# PMP9517.net
KiCad netlist of a schematic drawn in Altium Designer
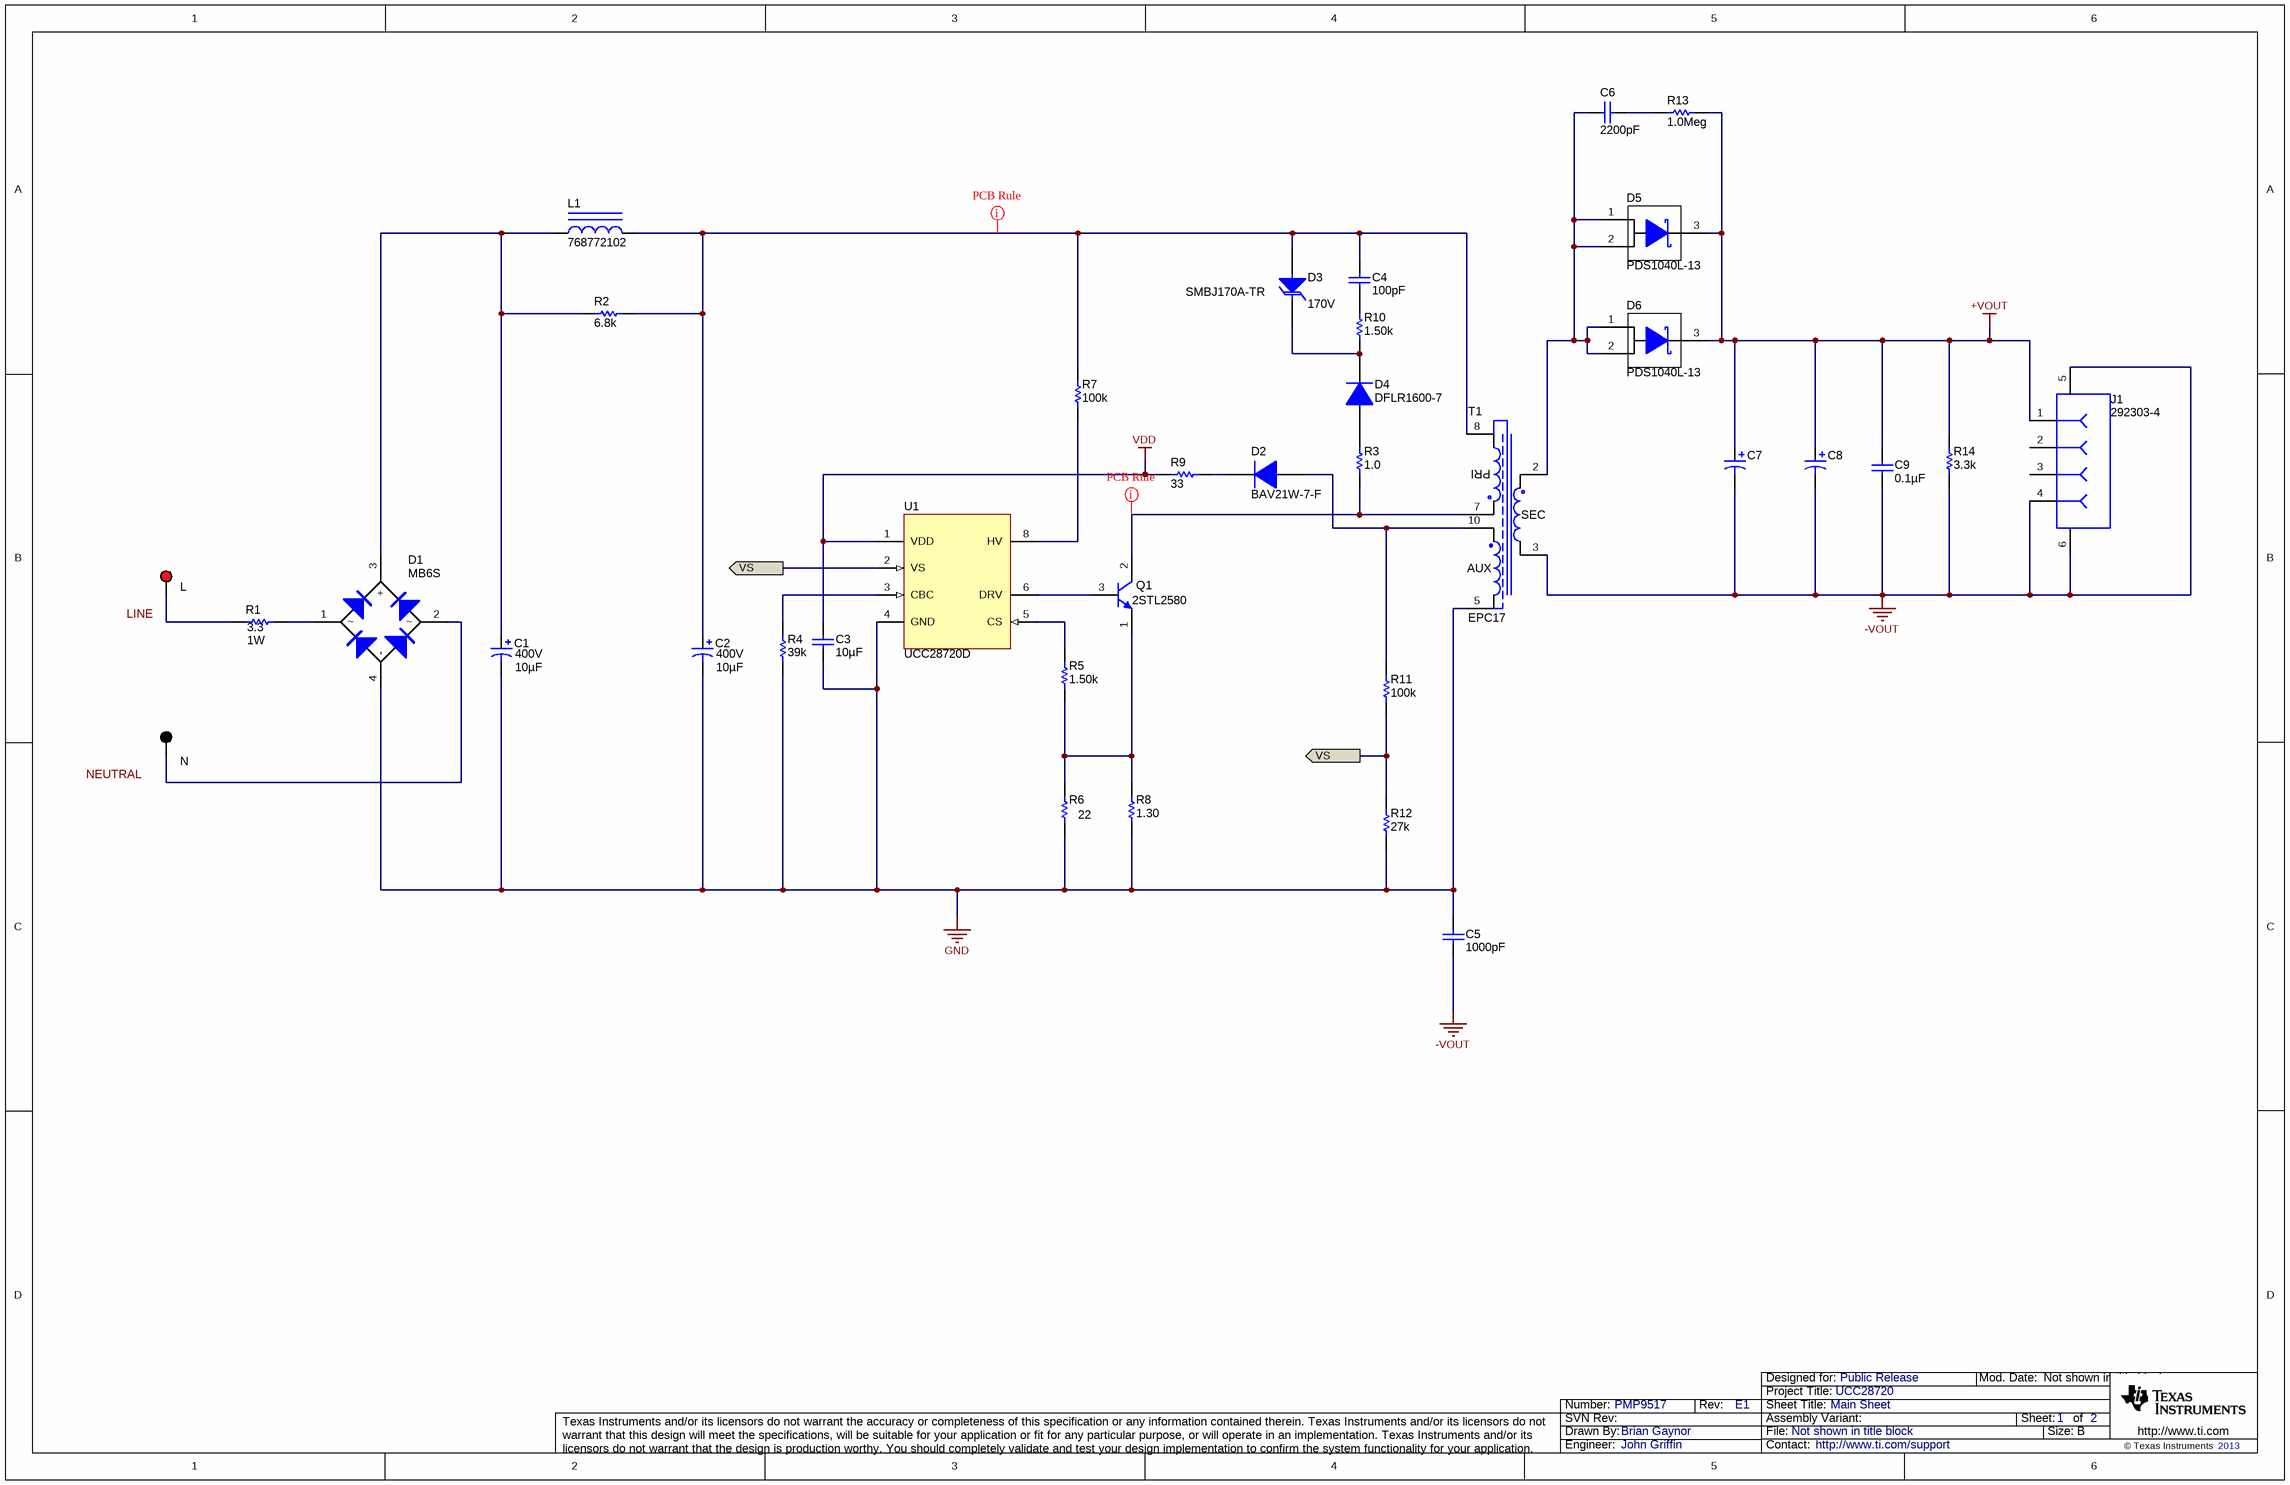
[diagram p0: PMP9517.SchDoc]

(export (version "E")
  (design (tool "Eeschema 10.0.6"))
  (components
    (comp (ref "C1")
      (value "10µF")
      (footprint "CAPPRD500W60D1000H1250")
      (description "CAP ALUM 10UF 400V 20% RADIAL")
      (fields (field (name "PARTNUMBER") "UVC2G100MPD") (field (name "VDC_V") "400V"))
      (libsource (lib "MiscParts") (part "Capacitor_Polarized"))
    )
    (comp (ref "C2")
      (value "10µF")
      (footprint "CAPPRD500W60D1000H1250")
      (description "CAP ALUM 10UF 400V 20% RADIAL")
      (fields (field (name "PARTNUMBER") "UVC2G100MPD") (field (name "VDC_V") "400V"))
      (libsource (lib "MiscParts") (part "Capacitor_Polarized"))
    )
    (comp (ref "C3")
      (value "1210YD106KAT2A")
      (footprint "1210")
      (description "CAP, CERM, 10uF, 16V, +/-10%, X5R, 1210")
      (fields
        (field (name "MANUFACTURER") "AVX")
        (field (name "VALUEDISPLAYED") "10µF")
        (field (name "PUBLISHER") "Texas Instruments")
      )
      (libsource (lib "Capacitor_Ceramic") (part "1210YD106KAT2A"))
    )
    (comp (ref "C4")
      (value "C1206C101JCGACTU")
      (footprint "1206")
      (description "CAP, CERM, 100pF, 500V, +/-5%, C0G/NP0, 1206")
      (fields
        (field (name "MANUFACTURER") "Kemet")
        (field (name "VALUEDISPLAYED") "100pF")
        (field (name "PUBLISHER") "Texas Instruments")
      )
      (libsource (lib "Capacitor_Ceramic") (part "C1206C101JCGACTU"))
    )
    (comp (ref "C5")
      (value "VY2102M29Y5UG63V7")
      (footprint "CAPRD750W60D750H1050")
      (description "CAP, CERM, 1000pF, 300V, +/-20%, Y5U, Radial Disc 7.5mm, ls=7.5")
      (fields
        (field (name "VALUEDISPLAYED") "1000pF")
        (field (name "MANUFACTURER") "Vishay-Bccomponents")
        (field (name "PUBLISHER") "Texas Instruments")
      )
      (libsource (lib "Capacitor_Ceramic") (part "VY2102M29Y5UG63V7"))
    )
    (comp (ref "C6")
      (value "08055C222KAT2A")
      (footprint "0805_HV")
      (description "CAP, CERM, 2200pF, 50V, +/-10%, X7R, 0805")
      (fields
        (field (name "VALUEDISPLAYED") "2200pF")
        (field (name "MANUFACTURER") "AVX")
        (field (name "PUBLISHER") "Texas Instruments")
      )
      (libsource (lib "Capacitor_Ceramic") (part "08055C222KAT2A"))
    )
    (comp (ref "C7")
      (value "RNE0J122MDN1PX")
      (footprint "NRE-AX_800x1080")
      (description "CAP ALUM 1200UF 6.3V 20% RADIAL")
      (fields (field (name "MANUFACTURER") "Nichicon"))
      (libsource (lib "MiscParts") (part "Capacitor_Polarized"))
    )
    (comp (ref "C8")
      (value "CAP ALUM 1200UF 6.3V 20% RADIAL")
      (footprint "NRE-AX_800x1080")
      (description "CAP, [Technology], xxxF, xxV, +/-xx%, xxOhm ESR, [MountType]")
      (fields (field (name "PARTNUMBER") "RNE0J122MDN1PX") (field (name "MANUFACTURER") "Nichicon"))
      (libsource (lib "MiscParts") (part "Capacitor_Polarized"))
    )
    (comp (ref "C9")
      (value "08055C104JAT2A")
      (footprint "0805_HV")
      (description "CAP, CERM, 0.1uF, 50V, +/-5%, X7R, 0805")
      (fields
        (field (name "VALUEDISPLAYED") "0.1µF")
        (field (name "MANUFACTURER") "AVX")
        (field (name "PUBLISHER") "Texas Instruments")
      )
      (libsource (lib "Capacitor_Ceramic") (part "08055C104JAT2A"))
    )
    (comp (ref "D1")
      (value "MB6S")
      (footprint "MiniDIP-MB6S")
      (description "Diode, Switching-Bridge, 600V, 1A, TH")
      (fields (field (name "PARTNUMBER") "MB6S"))
      (libsource (lib "PMP9045E1") (part "MB6S"))
    )
    (comp (ref "D2")
      (value "BAV21W-7-F")
      (footprint "SOD-123")
      (description "Diode, Switching, 200V, 0.2A, SOD-123")
      (fields
        (field (name "MANUFACTURER") "Diodes Inc.")
        (field (name "PARTNUMBER") "BAV21W-7-F")
        (field (name "PUBLISHER") "Texas Instruments")
      )
      (libsource (lib "Diode") (part "BAV21W-7-F"))
    )
    (comp (ref "D3")
      (value "SMBJ170A-TR")
      (footprint "SMB")
      (description "Diode, TVS, Uni, 170V, 600W, SMB")
      (fields
        (field (name "ALTIUM_VALUE") "170V")
        (field (name "MANUFACTURER") "ST Microelectronics")
        (field (name "PUBLISHER") "Texas Instruments")
      )
      (libsource (lib "ZenerDiodes") (part "SMBJ170A-TR"))
    )
    (comp (ref "D4")
      (value "DFLR1600-7")
      (footprint "powerDI123")
      (description "DIODE GP 600V 1A POWERDI123")
      (fields (field (name "MANUFACTURER") "Diodes Inc"))
      (libsource (lib "MiscParts") (part "Diode"))
    )
    (comp (ref "D5")
      (value "PDS1040L-13")
      (footprint "powerdi5")
      (description "DIODE SCHOTTKY 40V 10A POWERDI5")
      (fields (field (name "MANUFACTURER") "Diodes Inc"))
      (libsource (lib "Diode") (part "30WQ04FNPBF"))
    )
    (comp (ref "D6")
      (value "PDS1040L-13")
      (footprint "powerdi5")
      (description "DIODE SCHOTTKY 40V 10A POWERDI5")
      (fields (field (name "MANUFACTURER") "Diodes Inc"))
      (libsource (lib "Diode") (part "30WQ04FNPBF"))
    )
    (comp (ref "J1")
      (value "292303-4")
      (footprint "CONN_TE_292303-4")
      (description "Connector, USB Type A, Receptacle, R/A, TH")
      (fields
        (field (name "MANUFACTURER") "TE Connectivity")
        (field (name "SYMBOLCREATOR") "a0412235")
        (field (name "PUBLISHER") "Texas Instruments")
      )
      (libsource (lib "Connectors") (part "292303-4"))
    )
    (comp (ref "L")
      (value "5005")
      (footprint "Keystone5005")
      (description "Test Point, Compact, Red, TH")
      (fields (field (name "MANUFACTURER") "Keystone") (field (name "PUBLISHER") "Texas Instruments"))
      (libsource (lib "Connectors") (part "5005"))
    )
    (comp (ref "L1")
      (value "768772102")
      (footprint "IND_WE-TI_8095")
      (description "Inductor, Shielded Drum Core, Metal Composite, 1mH, 0.5A, 1.7 ohm, TH")
      (fields
        (field (name "MANUFACTURER") "Wurth Elektronik eiSos")
        (field (name "PUBLISHER") "Texas Instruments")
      )
      (libsource (lib "Inductor_Wurth") (part "768772102"))
    )
    (comp (ref "N")
      (value "5006")
      (footprint "Keystone5006")
      (description "Test Point, Compact, Black, TH")
      (fields (field (name "MANUFACTURER") "Keystone") (field (name "PUBLISHER") "Texas Instruments"))
      (libsource (lib "Connectors") (part "5006"))
    )
    (comp (ref "Q1")
      (value "2STL2580")
      (footprint "TO-92_AllBent")
      (description "Transistors Bipolar - BJT High Volt NPN Trans 800V Vces 400V Vceo")
      (fields (field (name "PARTNUMBER") "2STL2580") (field (name "MANUFACTURER") "STMicroelectronics"))
      (libsource (lib "Bipolar_Transistor") (part "STBV32-AP, ST Microelectronics"))
    )
    (comp (ref "R1")
      (value "3.3")
      (footprint "RES_ERG1S_V")
      (description "RES 3.3 OHM 1W 5% AXIAL")
      (fields (field (name "PARTNUMBER") "SPP1UL3R30JLF") (field (name "POWER_W") "1W"))
      (libsource (lib "MiscParts") (part "Resistor"))
    )
    (comp (ref "R2")
      (value "6.8k")
      (footprint "0805_HV")
      (description "RES, 6.8k ohm, 5%, 0.125W, 0805")
      (fields
        (field (name "PARTNUMBER") "CRCW08056K80JNEA")
        (field (name "MANUFACTURER") "Vishay-Dale")
        (field (name "PUBLISHER") "Texas Instruments")
      )
      (libsource (lib "Resistor_0805") (part "CRCW08056K80JNEA"))
    )
    (comp (ref "R3")
      (value "1.0")
      (footprint "1206")
      (description "RES, 1.0 ohm, 5%, 0.25W, 1206")
      (fields
        (field (name "PARTNUMBER") "CRCW12061R00JNEA")
        (field (name "MANUFACTURER") "Vishay-Dale")
        (field (name "PUBLISHER") "Texas Instruments")
      )
      (libsource (lib "Resistor_1206") (part "CRCW12061R00JNEA"))
    )
    (comp (ref "R4")
      (value "39k")
      (footprint "0603")
      (description "RES, 39k ohm, 5%, 0.1W, 0603")
      (fields
        (field (name "PARTNUMBER") "CRCW060339K0JNEA")
        (field (name "MANUFACTURER") "Vishay-Dale")
        (field (name "PUBLISHER") "Texas Instruments")
      )
      (libsource (lib "Resistor_0603") (part "CRCW060339K0JNEA"))
    )
    (comp (ref "R5")
      (value "1.50k")
      (footprint "0603")
      (description "RES, 1.50k ohm, 1%, 0.1W, 0603")
      (fields
        (field (name "PARTNUMBER") "CRCW06031K50FKEA")
        (field (name "MANUFACTURER") "Vishay-Dale")
        (field (name "PUBLISHER") "Texas Instruments")
      )
      (libsource (lib "Resistor_0603") (part "CRCW06031K50FKEA"))
    )
    (comp (ref "R6")
      (value "22")
      (footprint "2512M")
      (description "RES, 22 ohm, 5%, 1.5W, 2512")
      (fields
        (field (name "PARTNUMBER") "CRCW251222R0JNEGHP")
        (field (name "MANUFACTURER") "Vishay-Dale")
        (field (name "PUBLISHER") "Texas Instruments")
      )
      (libsource (lib "Resistor_OtherSMT") (part "CRCW251222R0JNEGHP"))
    )
    (comp (ref "R7")
      (value "100k")
      (footprint "1206")
      (description "RES, 100k ohm, 1%, 0.25W, 1206")
      (fields
        (field (name "PARTNUMBER") "RC1206FR-07100KL")
        (field (name "MANUFACTURER") "Yageo America")
        (field (name "PUBLISHER") "Texas Instruments")
      )
      (libsource (lib "Resistor_1206") (part "RC1206FR-07100KL"))
    )
    (comp (ref "R8")
      (value "1.30")
      (footprint "2512M")
      (description "RES, 1.30 ohm, 1%, 1W, 2512")
      (fields
        (field (name "PARTNUMBER") "ERJ-1TRQF1R3U")
        (field (name "MANUFACTURER") "Panasonic")
        (field (name "PUBLISHER") "Texas Instruments")
      )
      (libsource (lib "Resistor_OtherSMT") (part "ERJ-1TRQF1R3U"))
    )
    (comp (ref "R9")
      (value "33")
      (footprint "0603")
      (description "RES, 33 ohm, 5%, 0.1W, 0603")
      (fields
        (field (name "PARTNUMBER") "CRCW060333R0JNEA")
        (field (name "MANUFACTURER") "Vishay-Dale")
        (field (name "PUBLISHER") "Texas Instruments")
      )
      (libsource (lib "Resistor_0603") (part "CRCW060333R0JNEA"))
    )
    (comp (ref "R10")
      (value "1.50k")
      (footprint "1206")
      (description "RES, 1.50k ohm, 1%, 0.25W, 1206")
      (fields
        (field (name "PARTNUMBER") "CRCW12061K50FKEA")
        (field (name "MANUFACTURER") "Vishay-Dale")
        (field (name "PUBLISHER") "Texas Instruments")
      )
      (libsource (lib "Resistor_1206") (part "CRCW12061K50FKEA"))
    )
    (comp (ref "R11")
      (value "100k")
      (footprint "0603")
      (description "RES, 100k ohm, 1%, 0.1W, 0603")
      (fields
        (field (name "PARTNUMBER") "CRCW0603100KFKEA")
        (field (name "MANUFACTURER") "Vishay-Dale")
        (field (name "PUBLISHER") "Texas Instruments")
      )
      (libsource (lib "Resistor_0603") (part "CRCW0603100KFKEA"))
    )
    (comp (ref "R12")
      (value "27k")
      (footprint "0603")
      (description "RES, 27k ohm, 5%, 0.1W, 0603")
      (fields
        (field (name "PARTNUMBER") "RC0603JR-0727KL")
        (field (name "MANUFACTURER") "Yageo America")
        (field (name "PUBLISHER") "Texas Instruments")
      )
      (libsource (lib "Resistor_0603") (part "RC0603JR-0727KL"))
    )
    (comp (ref "R13")
      (value "1.0Meg")
      (footprint "0805_HV")
      (description "RES, 1.0Meg ohm, 5%, 0.125W, 0805")
      (fields
        (field (name "PARTNUMBER") "CRCW08051M00JNEA")
        (field (name "MANUFACTURER") "Vishay-Dale")
        (field (name "PUBLISHER") "Texas Instruments")
      )
      (libsource (lib "Resistor_0805") (part "CRCW08051M00JNEA"))
    )
    (comp (ref "R14")
      (value "3.3k")
      (footprint "0805_HV")
      (description "RES, 3.3k ohm, 5%, 0.125W, 0805")
      (fields
        (field (name "PARTNUMBER") "CRCW08053K30JNEA")
        (field (name "MANUFACTURER") "Vishay-Dale")
        (field (name "PUBLISHER") "Texas Instruments")
      )
      (libsource (lib "Resistor_0805") (part "CRCW08053K30JNEA"))
    )
    (comp (ref "T1")
      (value "EPC17")
      (footprint "MAG\\TH\\EPC17")
      (description "JohnGriffin")
      (fields (field (name "PARTNUMBER") "EPC17") (field (name "PUBLISHER") "Texas Instruments"))
      (libsource (lib "PMP-JG") (part "EPC17"))
    )
    (comp (ref "U1")
      (value "UCC28720D")
      (footprint "D0007A_N")
      (description "CONSTANT-VOLTAGE, CONSTANT-CURRENT CONTROLLER WITH PRIMARY SIDE REGULATION, D0007A")
      (fields
        (field (name "MANUFACTURER") "Texas Instruments")
        (field (name "SYMBOLCREATOR") "a0411947")
        (field (name "PUBLISHER") "Texas Instruments")
      )
      (libsource (lib "TI_Pre_Release") (part "UCC28720D"))
    )
  )
  (nets
    (net (code "1") (name "+VOUT") (class "Default")
      (node (ref "C7") (pin "1") (pinfunction "+_1") (pintype "passive"))
      (node (ref "C8") (pin "1") (pinfunction "+_1") (pintype "passive"))
      (node (ref "C9") (pin "2") (pinfunction "2_2") (pintype "passive"))
      (node (ref "D5") (pin "3") (pinfunction "K_3") (pintype "passive"))
      (node (ref "D6") (pin "3") (pinfunction "K_3") (pintype "passive"))
      (node (ref "J1") (pin "1") (pintype "passive"))
      (node (ref "R13") (pin "2") (pinfunction "2_2") (pintype "passive"))
      (node (ref "R14") (pin "2") (pinfunction "2_2") (pintype "passive"))
    )
    (net (code "2") (name "-VOUT") (class "Default")
      (node (ref "C5") (pin "2") (pinfunction "2_2") (pintype "passive"))
      (node (ref "C7") (pin "2") (pinfunction "-_2") (pintype "passive"))
      (node (ref "C8") (pin "2") (pinfunction "-_2") (pintype "passive"))
      (node (ref "C9") (pin "1") (pinfunction "1_1") (pintype "passive"))
      (node (ref "J1") (pin "4") (pintype "passive"))
      (node (ref "J1") (pin "5") (pintype "passive"))
      (node (ref "J1") (pin "6") (pintype "passive"))
      (node (ref "R14") (pin "1") (pinfunction "1_1") (pintype "passive"))
      (node (ref "T1") (pin "3") (pinfunction "3_3") (pintype "passive"))
    )
    (net (code "5") (name "/VS") (class "Default")
      (node (ref "R11") (pin "1") (pinfunction "1_1") (pintype "passive"))
      (node (ref "R12") (pin "2") (pinfunction "2_2") (pintype "passive"))
      (node (ref "U1") (pin "2") (pinfunction "VS_2") (pintype "input"))
    )
    (net (code "6") (name "GND") (class "Default")
      (node (ref "C1") (pin "2") (pinfunction "-_2") (pintype "passive"))
      (node (ref "C2") (pin "2") (pinfunction "-_2") (pintype "passive"))
      (node (ref "C3") (pin "2") (pinfunction "2_2") (pintype "passive"))
      (node (ref "C5") (pin "1") (pinfunction "1_1") (pintype "passive"))
      (node (ref "D1") (pin "4") (pinfunction "-_4") (pintype "passive"))
      (node (ref "R12") (pin "1") (pinfunction "1_1") (pintype "passive"))
      (node (ref "R4") (pin "1") (pinfunction "1_1") (pintype "passive"))
      (node (ref "R6") (pin "1") (pinfunction "1_1") (pintype "passive"))
      (node (ref "R8") (pin "1") (pinfunction "1_1") (pintype "passive"))
      (node (ref "T1") (pin "5") (pinfunction "5_5") (pintype "passive"))
      (node (ref "U1") (pin "4") (pinfunction "GND_4") (pintype "power_in"))
    )
    (net (code "7") (name "Net-(C1-+)") (class "Default")
      (node (ref "C1") (pin "1") (pinfunction "+_1") (pintype "passive"))
      (node (ref "D1") (pin "3") (pinfunction "+_3") (pintype "passive"))
      (node (ref "L1") (pin "1") (pinfunction "1_1") (pintype "passive"))
      (node (ref "R2") (pin "1") (pinfunction "1_1") (pintype "passive"))
    )
    (net (code "8") (name "Net-(C2-+)") (class "Default")
      (node (ref "C2") (pin "1") (pinfunction "+_1") (pintype "passive"))
      (node (ref "C4") (pin "1") (pinfunction "1_1") (pintype "passive"))
      (node (ref "D3") (pin "2") (pinfunction "A_2") (pintype "passive"))
      (node (ref "L1") (pin "2") (pinfunction "2_2") (pintype "passive"))
      (node (ref "R2") (pin "2") (pinfunction "2_2") (pintype "passive"))
      (node (ref "R7") (pin "1") (pinfunction "1_1") (pintype "passive"))
      (node (ref "T1") (pin "8") (pinfunction "8_8") (pintype "passive"))
    )
    (net (code "9") (name "Net-(C4-Pad2)") (class "Default")
      (node (ref "C4") (pin "2") (pinfunction "2_2") (pintype "passive"))
      (node (ref "R10") (pin "2") (pinfunction "2_2") (pintype "passive"))
    )
    (net (code "10") (name "Net-(C6-Pad1)") (class "Default")
      (node (ref "C6") (pin "1") (pinfunction "1_1") (pintype "passive"))
      (node (ref "D5") (pin "1") (pinfunction "A_1") (pintype "passive"))
      (node (ref "D5") (pin "2") (pinfunction "A_2") (pintype "passive"))
      (node (ref "D6") (pin "1") (pinfunction "A_1") (pintype "passive"))
      (node (ref "D6") (pin "2") (pinfunction "A_2") (pintype "passive"))
      (node (ref "T1") (pin "2") (pinfunction "2_2") (pintype "passive"))
    )
    (net (code "11") (name "Net-(C6-Pad2)") (class "Default")
      (node (ref "C6") (pin "2") (pinfunction "2_2") (pintype "passive"))
      (node (ref "R13") (pin "1") (pinfunction "1_1") (pintype "passive"))
    )
    (net (code "12") (name "Net-(D1-~-Pad1)") (class "Default")
      (node (ref "D1") (pin "1") (pinfunction "~_1") (pintype "passive"))
      (node (ref "R1") (pin "2") (pinfunction "2_2") (pintype "passive"))
    )
    (net (code "13") (name "Net-(D1-~-Pad2)") (class "Default")
      (node (ref "D1") (pin "2") (pinfunction "~_2") (pintype "passive"))
      (node (ref "N") (pin "1") (pintype "passive"))
    )
    (net (code "14") (name "Net-(D2-A)") (class "Default")
      (node (ref "D2") (pin "2") (pinfunction "A_2") (pintype "passive"))
      (node (ref "R11") (pin "2") (pinfunction "2_2") (pintype "passive"))
      (node (ref "T1") (pin "10") (pinfunction "10_10") (pintype "passive"))
    )
    (net (code "15") (name "Net-(D2-K)") (class "Default")
      (node (ref "D2") (pin "1") (pinfunction "K_1") (pintype "passive"))
      (node (ref "R9") (pin "2") (pinfunction "2_2") (pintype "passive"))
    )
    (net (code "16") (name "Net-(D3-K)") (class "Default")
      (node (ref "D3") (pin "1") (pinfunction "K_1") (pintype "passive"))
      (node (ref "D4") (pin "1") (pinfunction "K_1") (pintype "passive"))
      (node (ref "R10") (pin "1") (pinfunction "1_1") (pintype "passive"))
    )
    (net (code "17") (name "Net-(D4-A)") (class "Default")
      (node (ref "D4") (pin "2") (pinfunction "A_2") (pintype "passive"))
      (node (ref "R3") (pin "2") (pinfunction "2_2") (pintype "passive"))
    )
    (net (code "18") (name "Net-(L-Pad1)") (class "Default")
      (node (ref "L") (pin "1") (pintype "passive"))
      (node (ref "R1") (pin "1") (pinfunction "1_1") (pintype "passive"))
    )
    (net (code "19") (name "Net-(Q1-B)") (class "Default")
      (node (ref "Q1") (pin "1") (pinfunction "B_1") (pintype "passive"))
      (node (ref "R5") (pin "1") (pinfunction "1_1") (pintype "passive"))
      (node (ref "R6") (pin "2") (pinfunction "2_2") (pintype "passive"))
      (node (ref "R8") (pin "2") (pinfunction "2_2") (pintype "passive"))
    )
    (net (code "20") (name "Net-(Q1-C)") (class "Default")
      (node (ref "Q1") (pin "2") (pinfunction "C_2") (pintype "passive"))
      (node (ref "R3") (pin "1") (pinfunction "1_1") (pintype "passive"))
      (node (ref "T1") (pin "7") (pinfunction "7_7") (pintype "passive"))
    )
    (net (code "21") (name "Net-(Q1-E)") (class "Default")
      (node (ref "Q1") (pin "3") (pinfunction "E_3") (pintype "passive"))
      (node (ref "U1") (pin "6") (pinfunction "DRV_6") (pintype "power_in"))
    )
    (net (code "22") (name "Net-(U1-CBC)") (class "Default")
      (node (ref "R4") (pin "2") (pinfunction "2_2") (pintype "passive"))
      (node (ref "U1") (pin "3") (pinfunction "CBC_3") (pintype "input"))
    )
    (net (code "23") (name "Net-(U1-CS)") (class "Default")
      (node (ref "R5") (pin "2") (pinfunction "2_2") (pintype "passive"))
      (node (ref "U1") (pin "5") (pinfunction "CS_5") (pintype "input"))
    )
    (net (code "24") (name "Net-(U1-HV)") (class "Default")
      (node (ref "R7") (pin "2") (pinfunction "2_2") (pintype "passive"))
      (node (ref "U1") (pin "8") (pinfunction "HV_8") (pintype "power_in"))
    )
    (net (code "25") (name "VDD") (class "Default")
      (node (ref "C3") (pin "1") (pinfunction "1_1") (pintype "passive"))
      (node (ref "R9") (pin "1") (pinfunction "1_1") (pintype "passive"))
      (node (ref "U1") (pin "1") (pinfunction "VDD_1") (pintype "power_in"))
    )
    (net (code "26") (name "unconnected-(J1-Pad2)") (class "Default")
      (node (ref "J1") (pin "2") (pintype "passive"))
    )
    (net (code "27") (name "unconnected-(J1-Pad3)") (class "Default")
      (node (ref "J1") (pin "3") (pintype "passive"))
    )
  )
)
